# IR_Interface_Board.net
KiCad netlist of a schematic drawn in EAGLE
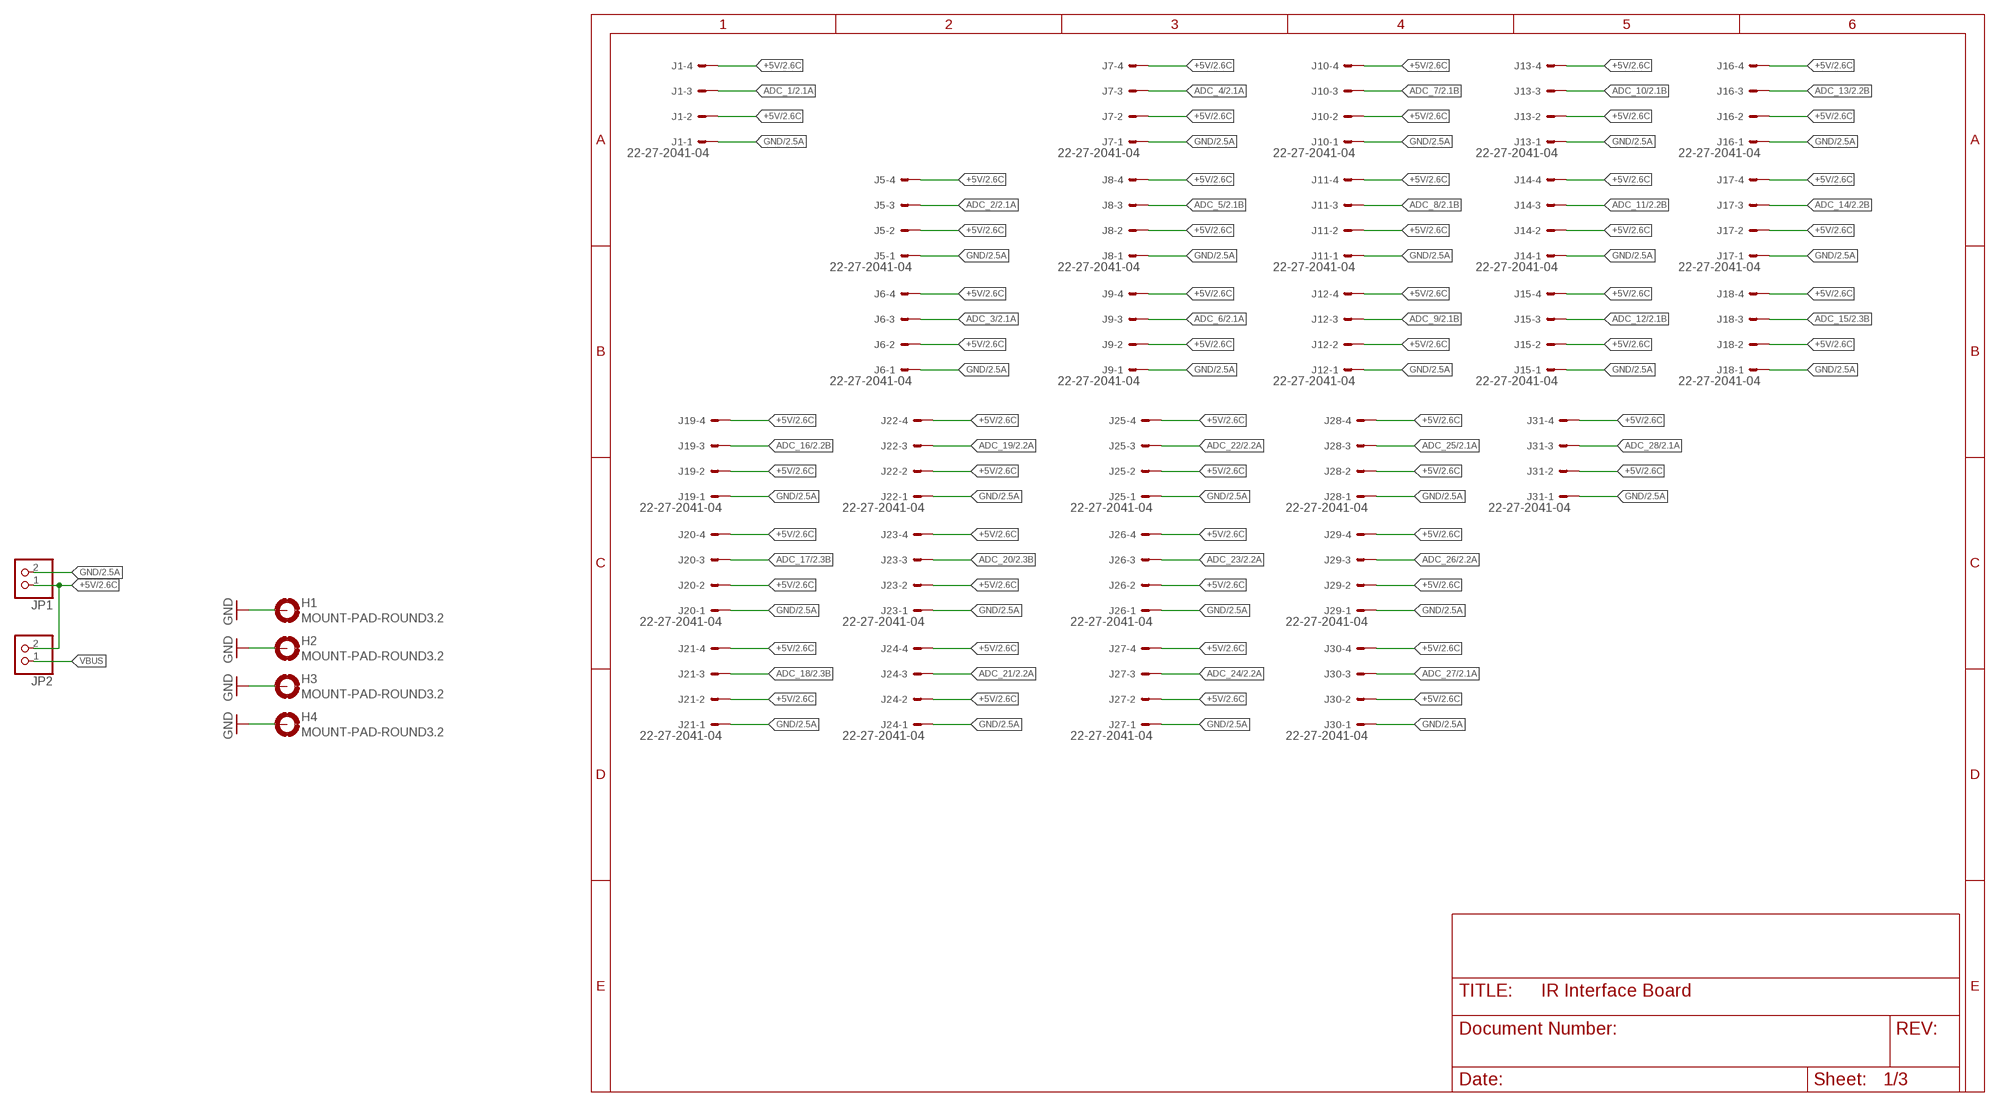
[diagram p0: schematic, sheet 1]
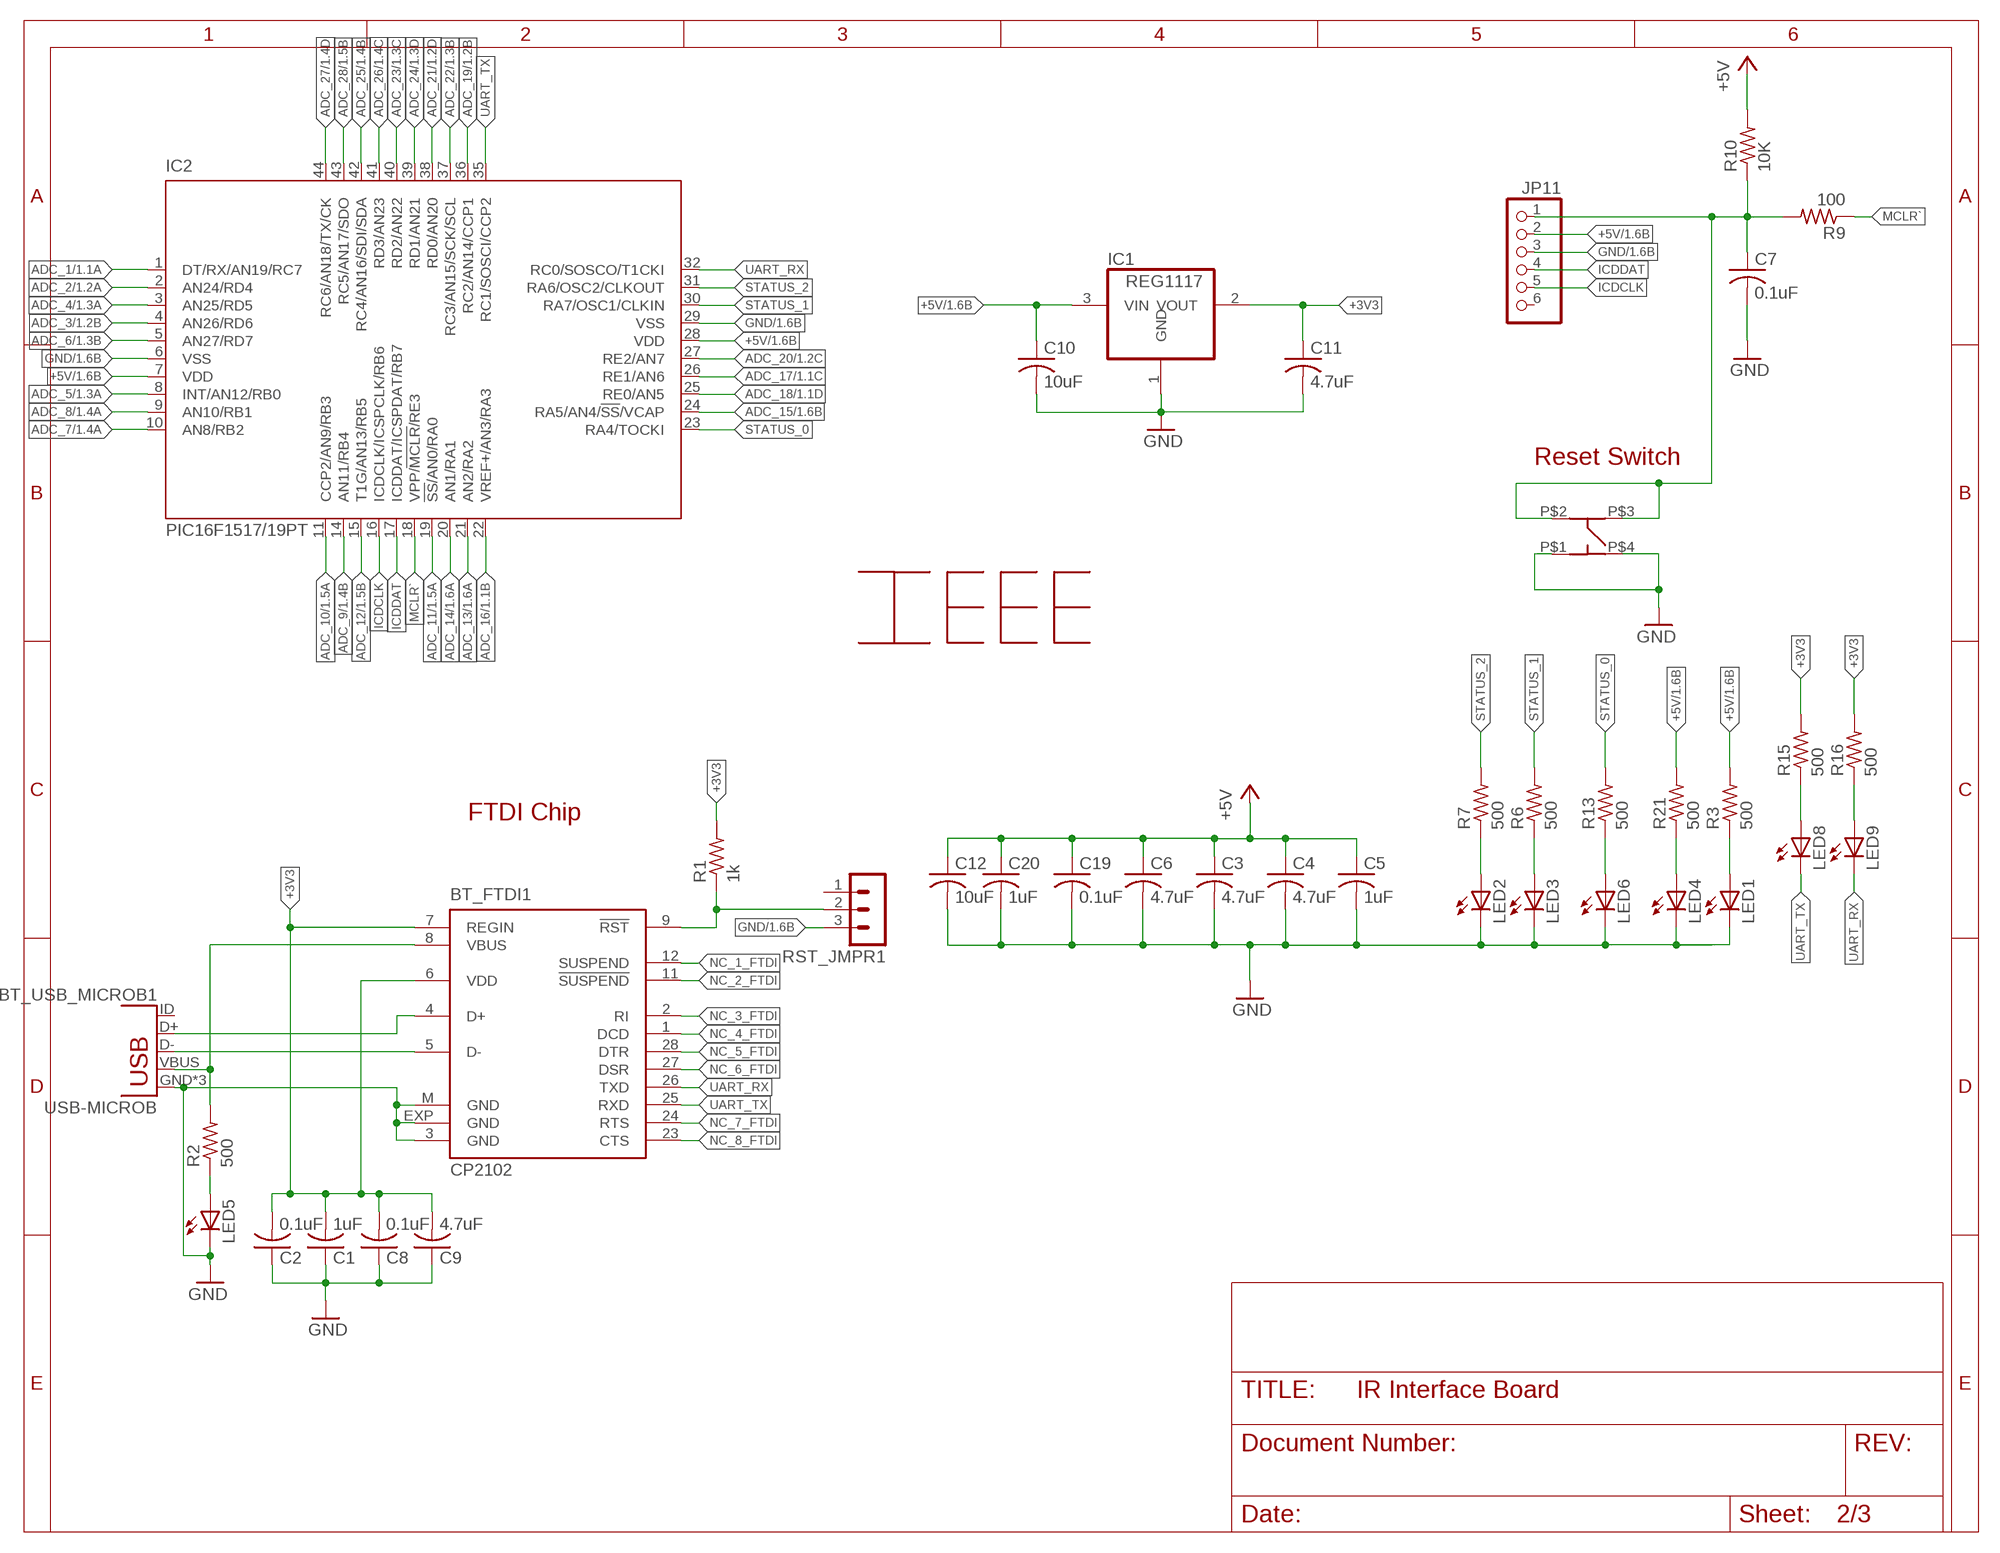
[diagram p1: schematic, sheet 2]
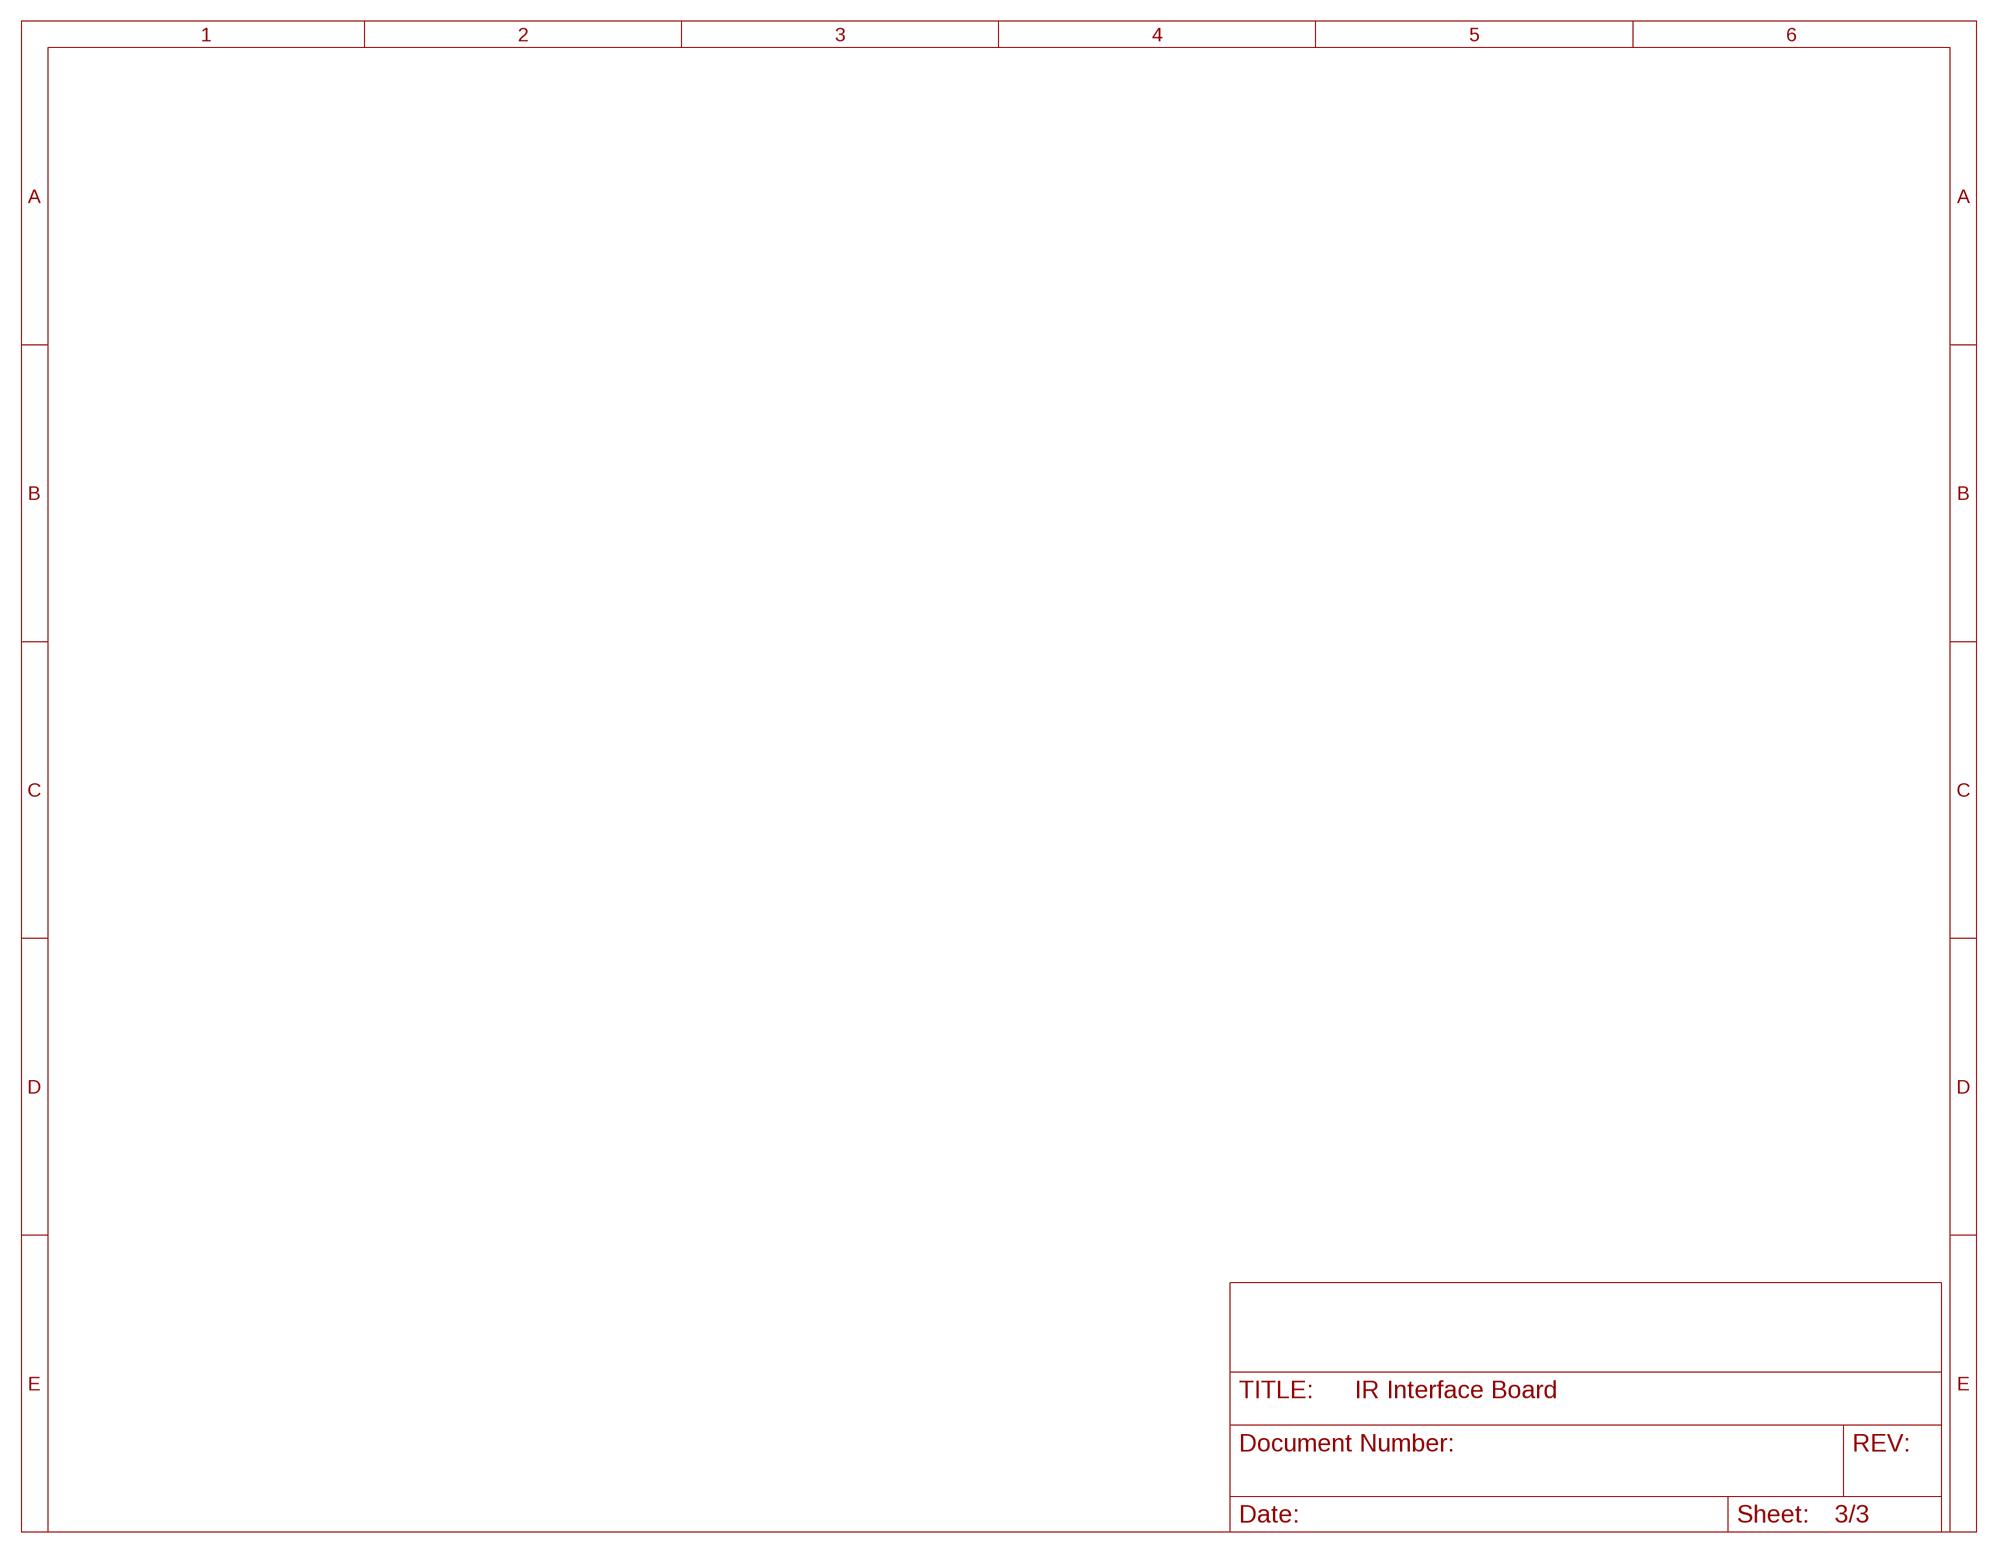
[diagram p2: schematic, sheet 3]

(export (version "E")
  (design (tool "Eeschema 10.0.6"))
  (components
    (comp (ref "H1")
      (value "MOUNT-PAD-ROUND3.2")
      (footprint "eagle-import:3,2-PAD")
      (libsource (lib "eagle-import") (part "MOUNT-PAD-ROUND3.2"))
    )
    (comp (ref "H2")
      (value "MOUNT-PAD-ROUND3.2")
      (footprint "eagle-import:3,2-PAD")
      (libsource (lib "eagle-import") (part "MOUNT-PAD-ROUND3.2"))
    )
    (comp (ref "H3")
      (value "MOUNT-PAD-ROUND3.2")
      (footprint "eagle-import:3,2-PAD")
      (libsource (lib "eagle-import") (part "MOUNT-PAD-ROUND3.2"))
    )
    (comp (ref "H4")
      (value "MOUNT-PAD-ROUND3.2")
      (footprint "eagle-import:3,2-PAD")
      (libsource (lib "eagle-import") (part "MOUNT-PAD-ROUND3.2"))
    )
    (comp (ref "J1")
      (value "22-27-2041-04")
      (footprint "eagle-import:6410-04")
      (libsource (lib "eagle-import") (part "22-?-0427-2041"))
    )
    (comp (ref "J5")
      (value "22-27-2041-04")
      (footprint "eagle-import:6410-04")
      (libsource (lib "eagle-import") (part "22-?-0427-2041"))
    )
    (comp (ref "J6")
      (value "22-27-2041-04")
      (footprint "eagle-import:6410-04")
      (libsource (lib "eagle-import") (part "22-?-0427-2041"))
    )
    (comp (ref "J7")
      (value "22-27-2041-04")
      (footprint "eagle-import:6410-04")
      (libsource (lib "eagle-import") (part "22-?-0427-2041"))
    )
    (comp (ref "J8")
      (value "22-27-2041-04")
      (footprint "eagle-import:6410-04")
      (libsource (lib "eagle-import") (part "22-?-0427-2041"))
    )
    (comp (ref "J9")
      (value "22-27-2041-04")
      (footprint "eagle-import:6410-04")
      (libsource (lib "eagle-import") (part "22-?-0427-2041"))
    )
    (comp (ref "J10")
      (value "22-27-2041-04")
      (footprint "eagle-import:6410-04")
      (libsource (lib "eagle-import") (part "22-?-0427-2041"))
    )
    (comp (ref "J11")
      (value "22-27-2041-04")
      (footprint "eagle-import:6410-04")
      (libsource (lib "eagle-import") (part "22-?-0427-2041"))
    )
    (comp (ref "J12")
      (value "22-27-2041-04")
      (footprint "eagle-import:6410-04")
      (libsource (lib "eagle-import") (part "22-?-0427-2041"))
    )
    (comp (ref "J13")
      (value "22-27-2041-04")
      (footprint "eagle-import:6410-04")
      (libsource (lib "eagle-import") (part "22-?-0427-2041"))
    )
    (comp (ref "J14")
      (value "22-27-2041-04")
      (footprint "eagle-import:6410-04")
      (libsource (lib "eagle-import") (part "22-?-0427-2041"))
    )
    (comp (ref "J15")
      (value "22-27-2041-04")
      (footprint "eagle-import:6410-04")
      (libsource (lib "eagle-import") (part "22-?-0427-2041"))
    )
    (comp (ref "J16")
      (value "22-27-2041-04")
      (footprint "eagle-import:6410-04")
      (libsource (lib "eagle-import") (part "22-?-0427-2041"))
    )
    (comp (ref "J17")
      (value "22-27-2041-04")
      (footprint "eagle-import:6410-04")
      (libsource (lib "eagle-import") (part "22-?-0427-2041"))
    )
    (comp (ref "J18")
      (value "22-27-2041-04")
      (footprint "eagle-import:6410-04")
      (libsource (lib "eagle-import") (part "22-?-0427-2041"))
    )
    (comp (ref "J19")
      (value "22-27-2041-04")
      (footprint "eagle-import:6410-04")
      (libsource (lib "eagle-import") (part "22-?-0427-2041"))
    )
    (comp (ref "J20")
      (value "22-27-2041-04")
      (footprint "eagle-import:6410-04")
      (libsource (lib "eagle-import") (part "22-?-0427-2041"))
    )
    (comp (ref "J21")
      (value "22-27-2041-04")
      (footprint "eagle-import:6410-04")
      (libsource (lib "eagle-import") (part "22-?-0427-2041"))
    )
    (comp (ref "J22")
      (value "22-27-2041-04")
      (footprint "eagle-import:6410-04")
      (libsource (lib "eagle-import") (part "22-?-0427-2041"))
    )
    (comp (ref "J23")
      (value "22-27-2041-04")
      (footprint "eagle-import:6410-04")
      (libsource (lib "eagle-import") (part "22-?-0427-2041"))
    )
    (comp (ref "J24")
      (value "22-27-2041-04")
      (footprint "eagle-import:6410-04")
      (libsource (lib "eagle-import") (part "22-?-0427-2041"))
    )
    (comp (ref "J25")
      (value "22-27-2041-04")
      (footprint "eagle-import:6410-04")
      (libsource (lib "eagle-import") (part "22-?-0427-2041"))
    )
    (comp (ref "J26")
      (value "22-27-2041-04")
      (footprint "eagle-import:6410-04")
      (libsource (lib "eagle-import") (part "22-?-0427-2041"))
    )
    (comp (ref "J27")
      (value "22-27-2041-04")
      (footprint "eagle-import:6410-04")
      (libsource (lib "eagle-import") (part "22-?-0427-2041"))
    )
    (comp (ref "J28")
      (value "22-27-2041-04")
      (footprint "eagle-import:6410-04")
      (libsource (lib "eagle-import") (part "22-?-0427-2041"))
    )
    (comp (ref "J29")
      (value "22-27-2041-04")
      (footprint "eagle-import:6410-04")
      (libsource (lib "eagle-import") (part "22-?-0427-2041"))
    )
    (comp (ref "J30")
      (value "22-27-2041-04")
      (footprint "eagle-import:6410-04")
      (libsource (lib "eagle-import") (part "22-?-0427-2041"))
    )
    (comp (ref "J31")
      (value "22-27-2041-04")
      (footprint "eagle-import:6410-04")
      (libsource (lib "eagle-import") (part "22-?-0427-2041"))
    )
    (comp (ref "JP1")
      (value "PINHD-1X2")
      (footprint "eagle-import:1X02")
      (libsource (lib "eagle-import") (part "PINHD-1X2"))
    )
    (comp (ref "JP2")
      (value "PINHD-1X2")
      (footprint "eagle-import:1X02")
      (libsource (lib "eagle-import") (part "PINHD-1X2"))
    )
    (comp (ref "BT_FTDI1")
      (value "CP2102")
      (footprint "eagle-import:MLP28")
      (fields (field (name "MF") "FARNELL") (field (name "MPN") "CP2102-GM"))
      (libsource (lib "eagle-import") (part "CP2102"))
    )
    (comp (ref "BT_USB_MICROB1")
      (value "USB-MICROB")
      (footprint "eagle-import:USB-MICROB")
      (libsource (lib "eagle-import") (part "USB-MICROB"))
    )
    (comp (ref "C1")
      (value "1uF")
      (footprint "eagle-import:C0805")
      (libsource (lib "eagle-import") (part "C-USC0805"))
    )
    (comp (ref "C2")
      (value "0.1uF")
      (footprint "eagle-import:C0805")
      (libsource (lib "eagle-import") (part "C-USC0805"))
    )
    (comp (ref "C3")
      (value "4.7uF")
      (footprint "eagle-import:C0805")
      (libsource (lib "eagle-import") (part "C-USC0805"))
    )
    (comp (ref "C4")
      (value "4.7uF")
      (footprint "eagle-import:C0805")
      (libsource (lib "eagle-import") (part "C-USC0805"))
    )
    (comp (ref "C5")
      (value "1uF")
      (footprint "eagle-import:C0805")
      (libsource (lib "eagle-import") (part "C-USC0805"))
    )
    (comp (ref "C6")
      (value "4.7uF")
      (footprint "eagle-import:C0805")
      (libsource (lib "eagle-import") (part "C-USC0805"))
    )
    (comp (ref "C7")
      (value "0.1uF")
      (footprint "eagle-import:C0805")
      (libsource (lib "eagle-import") (part "C-USC0805"))
    )
    (comp (ref "C8")
      (value "0.1uF")
      (footprint "eagle-import:C0805")
      (libsource (lib "eagle-import") (part "C-USC0805"))
    )
    (comp (ref "C9")
      (value "4.7uF")
      (footprint "eagle-import:C0805")
      (libsource (lib "eagle-import") (part "C-USC0805"))
    )
    (comp (ref "C10")
      (value "10uF")
      (footprint "eagle-import:C0805")
      (libsource (lib "eagle-import") (part "C-USC0805"))
    )
    (comp (ref "C11")
      (value "4.7uF")
      (footprint "eagle-import:C0805")
      (libsource (lib "eagle-import") (part "C-USC0805"))
    )
    (comp (ref "C12")
      (value "10uF")
      (footprint "eagle-import:C0805")
      (libsource (lib "eagle-import") (part "C-USC0805"))
    )
    (comp (ref "C19")
      (value "0.1uF")
      (footprint "eagle-import:C0805")
      (libsource (lib "eagle-import") (part "C-USC0805"))
    )
    (comp (ref "C20")
      (value "1uF")
      (footprint "eagle-import:C0805")
      (libsource (lib "eagle-import") (part "C-USC0805"))
    )
    (comp (ref "IC1")
      (value "REG1117")
      (footprint "eagle-import:SOT223")
      (libsource (lib "eagle-import") (part "REG1117"))
    )
    (comp (ref "IC2")
      (value "PIC16F1517/19PT")
      (footprint "eagle-import:TQFP44")
      (libsource (lib "eagle-import") (part "PIC16F1517/19PT"))
    )
    (comp (ref "JP11")
      (value "PINHD-1X6/90")
      (footprint "eagle-import:1X06_90")
      (libsource (lib "eagle-import") (part "PINHD-1X6/90"))
    )
    (comp (ref "LED1")
      (value "LEDSML0603")
      (footprint "eagle-import:SML0603")
      (libsource (lib "eagle-import") (part "LEDSML0603"))
    )
    (comp (ref "LED2")
      (value "LEDSML0603")
      (footprint "eagle-import:SML0603")
      (libsource (lib "eagle-import") (part "LEDSML0603"))
    )
    (comp (ref "LED3")
      (value "LEDSML0603")
      (footprint "eagle-import:SML0603")
      (libsource (lib "eagle-import") (part "LEDSML0603"))
    )
    (comp (ref "LED4")
      (value "LEDSML0603")
      (footprint "eagle-import:SML0603")
      (libsource (lib "eagle-import") (part "LEDSML0603"))
    )
    (comp (ref "LED5")
      (value "LEDSML0603")
      (footprint "eagle-import:SML0603")
      (libsource (lib "eagle-import") (part "LEDSML0603"))
    )
    (comp (ref "LED6")
      (value "LEDSML0603")
      (footprint "eagle-import:SML0603")
      (libsource (lib "eagle-import") (part "LEDSML0603"))
    )
    (comp (ref "LED8")
      (value "LEDSML0603")
      (footprint "eagle-import:SML0603")
      (libsource (lib "eagle-import") (part "LEDSML0603"))
    )
    (comp (ref "LED9")
      (value "LEDSML0603")
      (footprint "eagle-import:SML0603")
      (libsource (lib "eagle-import") (part "LEDSML0603"))
    )
    (comp (ref "R1")
      (value "1k")
      (footprint "eagle-import:R0805")
      (libsource (lib "eagle-import") (part "resistor_R-US_R0805"))
    )
    (comp (ref "R2")
      (value "500")
      (footprint "eagle-import:R0805")
      (libsource (lib "eagle-import") (part "R-US_R0805"))
    )
    (comp (ref "R3")
      (value "500")
      (footprint "eagle-import:R0805")
      (libsource (lib "eagle-import") (part "R-US_R0805"))
    )
    (comp (ref "R6")
      (value "500")
      (footprint "eagle-import:R0805")
      (libsource (lib "eagle-import") (part "R-US_R0805"))
    )
    (comp (ref "R7")
      (value "500")
      (footprint "eagle-import:R0805")
      (libsource (lib "eagle-import") (part "R-US_R0805"))
    )
    (comp (ref "R9")
      (value "100")
      (footprint "eagle-import:R0805")
      (libsource (lib "eagle-import") (part "R-US_R0805"))
    )
    (comp (ref "R10")
      (value "10K")
      (footprint "eagle-import:R0805")
      (libsource (lib "eagle-import") (part "R-US_R0805"))
    )
    (comp (ref "R13")
      (value "500")
      (footprint "eagle-import:R0805")
      (libsource (lib "eagle-import") (part "R-US_R0805"))
    )
    (comp (ref "R15")
      (value "500")
      (footprint "eagle-import:R0805")
      (libsource (lib "eagle-import") (part "R-US_R0805"))
    )
    (comp (ref "R16")
      (value "500")
      (footprint "eagle-import:R0805")
      (libsource (lib "eagle-import") (part "R-US_R0805"))
    )
    (comp (ref "R21")
      (value "500")
      (footprint "eagle-import:R0805")
      (libsource (lib "eagle-import") (part "R-US_R0805"))
    )
    (comp (ref "RST_JMPR1")
      (value "MA03-1")
      (footprint "eagle-import:MA03-1")
      (libsource (lib "eagle-import") (part "MA03-1"))
    )
    (comp (ref "TOUCH_RESET")
      (value "RESET")
      (footprint "eagle-import:MC32882_FINAL")
      (libsource (lib "eagle-import") (part "MC32882_SW"))
    )
    (comp (ref "U$1")
      (value "LOGO")
      (footprint "eagle-import:IEEE-LOGO")
      (libsource (lib "eagle-import") (part "LOGO"))
    )
  )
  (nets
    (net (code "1") (name "+3V3") (class "Default")
      (node (ref "BT_FTDI1") (pin "6") (pinfunction "VDD_6") (pintype "power_in"))
      (node (ref "BT_FTDI1") (pin "7") (pinfunction "REGIN_7") (pintype "passive"))
      (node (ref "C1") (pin "2") (pinfunction "2_2") (pintype "passive"))
      (node (ref "C11") (pin "1") (pinfunction "1_1") (pintype "passive"))
      (node (ref "C2") (pin "2") (pinfunction "2_2") (pintype "passive"))
      (node (ref "C8") (pin "2") (pinfunction "2_2") (pintype "passive"))
      (node (ref "C9") (pin "2") (pinfunction "2_2") (pintype "passive"))
      (node (ref "IC1") (pin "2") (pinfunction "VOUT_2") (pintype "output"))
      (node (ref "R1") (pin "2") (pinfunction "2_2") (pintype "passive"))
      (node (ref "R15") (pin "2") (pinfunction "2_2") (pintype "passive"))
      (node (ref "R16") (pin "2") (pinfunction "2_2") (pintype "passive"))
    )
    (net (code "2") (name "+5V") (class "Default")
      (node (ref "C10") (pin "1") (pinfunction "1_1") (pintype "passive"))
      (node (ref "C12") (pin "1") (pinfunction "1_1") (pintype "passive"))
      (node (ref "C19") (pin "1") (pinfunction "1_1") (pintype "passive"))
      (node (ref "C20") (pin "1") (pinfunction "1_1") (pintype "passive"))
      (node (ref "C3") (pin "1") (pinfunction "1_1") (pintype "passive"))
      (node (ref "C4") (pin "1") (pinfunction "1_1") (pintype "passive"))
      (node (ref "C5") (pin "1") (pinfunction "1_1") (pintype "passive"))
      (node (ref "C6") (pin "1") (pinfunction "1_1") (pintype "passive"))
      (node (ref "IC1") (pin "3") (pinfunction "VIN_3") (pintype "input"))
      (node (ref "IC2") (pin "28") (pinfunction "VDD_28") (pintype "power_in"))
      (node (ref "IC2") (pin "7") (pinfunction "VDD_7") (pintype "power_in"))
      (node (ref "J1") (pin "2") (pinfunction "S_2") (pintype "passive"))
      (node (ref "J1") (pin "4") (pinfunction "S_4") (pintype "passive"))
      (node (ref "J10") (pin "2") (pinfunction "S_2") (pintype "passive"))
      (node (ref "J10") (pin "4") (pinfunction "S_4") (pintype "passive"))
      (node (ref "J11") (pin "2") (pinfunction "S_2") (pintype "passive"))
      (node (ref "J11") (pin "4") (pinfunction "S_4") (pintype "passive"))
      (node (ref "J12") (pin "2") (pinfunction "S_2") (pintype "passive"))
      (node (ref "J12") (pin "4") (pinfunction "S_4") (pintype "passive"))
      (node (ref "J13") (pin "2") (pinfunction "S_2") (pintype "passive"))
      (node (ref "J13") (pin "4") (pinfunction "S_4") (pintype "passive"))
      (node (ref "J14") (pin "2") (pinfunction "S_2") (pintype "passive"))
      (node (ref "J14") (pin "4") (pinfunction "S_4") (pintype "passive"))
      (node (ref "J15") (pin "2") (pinfunction "S_2") (pintype "passive"))
      (node (ref "J15") (pin "4") (pinfunction "S_4") (pintype "passive"))
      (node (ref "J16") (pin "2") (pinfunction "S_2") (pintype "passive"))
      (node (ref "J16") (pin "4") (pinfunction "S_4") (pintype "passive"))
      (node (ref "J17") (pin "2") (pinfunction "S_2") (pintype "passive"))
      (node (ref "J17") (pin "4") (pinfunction "S_4") (pintype "passive"))
      (node (ref "J18") (pin "2") (pinfunction "S_2") (pintype "passive"))
      (node (ref "J18") (pin "4") (pinfunction "S_4") (pintype "passive"))
      (node (ref "J19") (pin "2") (pinfunction "S_2") (pintype "passive"))
      (node (ref "J19") (pin "4") (pinfunction "S_4") (pintype "passive"))
      (node (ref "J20") (pin "2") (pinfunction "S_2") (pintype "passive"))
      (node (ref "J20") (pin "4") (pinfunction "S_4") (pintype "passive"))
      (node (ref "J21") (pin "2") (pinfunction "S_2") (pintype "passive"))
      (node (ref "J21") (pin "4") (pinfunction "S_4") (pintype "passive"))
      (node (ref "J22") (pin "2") (pinfunction "S_2") (pintype "passive"))
      (node (ref "J22") (pin "4") (pinfunction "S_4") (pintype "passive"))
      (node (ref "J23") (pin "2") (pinfunction "S_2") (pintype "passive"))
      (node (ref "J23") (pin "4") (pinfunction "S_4") (pintype "passive"))
      (node (ref "J24") (pin "2") (pinfunction "S_2") (pintype "passive"))
      (node (ref "J24") (pin "4") (pinfunction "S_4") (pintype "passive"))
      (node (ref "J25") (pin "2") (pinfunction "S_2") (pintype "passive"))
      (node (ref "J25") (pin "4") (pinfunction "S_4") (pintype "passive"))
      (node (ref "J26") (pin "2") (pinfunction "S_2") (pintype "passive"))
      (node (ref "J26") (pin "4") (pinfunction "S_4") (pintype "passive"))
      (node (ref "J27") (pin "2") (pinfunction "S_2") (pintype "passive"))
      (node (ref "J27") (pin "4") (pinfunction "S_4") (pintype "passive"))
      (node (ref "J28") (pin "2") (pinfunction "S_2") (pintype "passive"))
      (node (ref "J28") (pin "4") (pinfunction "S_4") (pintype "passive"))
      (node (ref "J29") (pin "2") (pinfunction "S_2") (pintype "passive"))
      (node (ref "J29") (pin "4") (pinfunction "S_4") (pintype "passive"))
      (node (ref "J30") (pin "2") (pinfunction "S_2") (pintype "passive"))
      (node (ref "J30") (pin "4") (pinfunction "S_4") (pintype "passive"))
      (node (ref "J31") (pin "2") (pinfunction "S_2") (pintype "passive"))
      (node (ref "J31") (pin "4") (pinfunction "S_4") (pintype "passive"))
      (node (ref "J5") (pin "2") (pinfunction "S_2") (pintype "passive"))
      (node (ref "J5") (pin "4") (pinfunction "S_4") (pintype "passive"))
      (node (ref "J6") (pin "2") (pinfunction "S_2") (pintype "passive"))
      (node (ref "J6") (pin "4") (pinfunction "S_4") (pintype "passive"))
      (node (ref "J7") (pin "2") (pinfunction "S_2") (pintype "passive"))
      (node (ref "J7") (pin "4") (pinfunction "S_4") (pintype "passive"))
      (node (ref "J8") (pin "2") (pinfunction "S_2") (pintype "passive"))
      (node (ref "J8") (pin "4") (pinfunction "S_4") (pintype "passive"))
      (node (ref "J9") (pin "2") (pinfunction "S_2") (pintype "passive"))
      (node (ref "J9") (pin "4") (pinfunction "S_4") (pintype "passive"))
      (node (ref "JP1") (pin "1") (pinfunction "1_1") (pintype "passive"))
      (node (ref "JP11") (pin "2") (pinfunction "2_2") (pintype "passive"))
      (node (ref "JP2") (pin "2") (pinfunction "2_2") (pintype "passive"))
      (node (ref "R10") (pin "2") (pinfunction "2_2") (pintype "passive"))
      (node (ref "R21") (pin "2") (pinfunction "2_2") (pintype "passive"))
      (node (ref "R3") (pin "2") (pinfunction "2_2") (pintype "passive"))
    )
    (net (code "3") (name "ADC_1") (class "Default")
      (node (ref "IC2") (pin "1") (pinfunction "DT/RX/AN19/RC7_1") (pintype "bidirectional"))
      (node (ref "J1") (pin "3") (pinfunction "S_3") (pintype "passive"))
    )
    (net (code "4") (name "ADC_2") (class "Default")
      (node (ref "IC2") (pin "2") (pinfunction "AN24/RD4_2") (pintype "bidirectional"))
      (node (ref "J5") (pin "3") (pinfunction "S_3") (pintype "passive"))
    )
    (net (code "5") (name "ADC_3") (class "Default")
      (node (ref "IC2") (pin "4") (pinfunction "AN26/RD6_4") (pintype "bidirectional"))
      (node (ref "J6") (pin "3") (pinfunction "S_3") (pintype "passive"))
    )
    (net (code "6") (name "ADC_4") (class "Default")
      (node (ref "IC2") (pin "3") (pinfunction "AN25/RD5_3") (pintype "bidirectional"))
      (node (ref "J7") (pin "3") (pinfunction "S_3") (pintype "passive"))
    )
    (net (code "7") (name "ADC_5") (class "Default")
      (node (ref "IC2") (pin "8") (pinfunction "INT/AN12/RB0_8") (pintype "bidirectional"))
      (node (ref "J8") (pin "3") (pinfunction "S_3") (pintype "passive"))
    )
    (net (code "8") (name "ADC_6") (class "Default")
      (node (ref "IC2") (pin "5") (pinfunction "AN27/RD7_5") (pintype "bidirectional"))
      (node (ref "J9") (pin "3") (pinfunction "S_3") (pintype "passive"))
    )
    (net (code "9") (name "ADC_7") (class "Default")
      (node (ref "IC2") (pin "10") (pinfunction "AN8/RB2_10") (pintype "bidirectional"))
      (node (ref "J10") (pin "3") (pinfunction "S_3") (pintype "passive"))
    )
    (net (code "10") (name "ADC_8") (class "Default")
      (node (ref "IC2") (pin "9") (pinfunction "AN10/RB1_9") (pintype "bidirectional"))
      (node (ref "J11") (pin "3") (pinfunction "S_3") (pintype "passive"))
    )
    (net (code "11") (name "ADC_9") (class "Default")
      (node (ref "IC2") (pin "14") (pinfunction "AN11/RB4_14") (pintype "bidirectional"))
      (node (ref "J12") (pin "3") (pinfunction "S_3") (pintype "passive"))
    )
    (net (code "12") (name "ADC_10") (class "Default")
      (node (ref "IC2") (pin "11") (pinfunction "CCP2/AN9/RB3_11") (pintype "bidirectional"))
      (node (ref "J13") (pin "3") (pinfunction "S_3") (pintype "passive"))
    )
    (net (code "13") (name "ADC_11") (class "Default")
      (node (ref "IC2") (pin "19") (pinfunction "~{SS}/AN0/RA0_19") (pintype "bidirectional"))
      (node (ref "J14") (pin "3") (pinfunction "S_3") (pintype "passive"))
    )
    (net (code "14") (name "ADC_12") (class "Default")
      (node (ref "IC2") (pin "15") (pinfunction "T1G/AN13/RB5_15") (pintype "bidirectional"))
      (node (ref "J15") (pin "3") (pinfunction "S_3") (pintype "passive"))
    )
    (net (code "15") (name "ADC_13") (class "Default")
      (node (ref "IC2") (pin "21") (pinfunction "AN2/RA2_21") (pintype "bidirectional"))
      (node (ref "J16") (pin "3") (pinfunction "S_3") (pintype "passive"))
    )
    (net (code "16") (name "ADC_14") (class "Default")
      (node (ref "IC2") (pin "20") (pinfunction "AN1/RA1_20") (pintype "bidirectional"))
      (node (ref "J17") (pin "3") (pinfunction "S_3") (pintype "passive"))
    )
    (net (code "17") (name "ADC_15") (class "Default")
      (node (ref "IC2") (pin "24") (pinfunction "RA5/AN4/~{SS}/VCAP_24") (pintype "bidirectional"))
      (node (ref "J18") (pin "3") (pinfunction "S_3") (pintype "passive"))
    )
    (net (code "18") (name "ADC_16") (class "Default")
      (node (ref "IC2") (pin "22") (pinfunction "VREF+/AN3/RA3_22") (pintype "bidirectional"))
      (node (ref "J19") (pin "3") (pinfunction "S_3") (pintype "passive"))
    )
    (net (code "19") (name "ADC_17") (class "Default")
      (node (ref "IC2") (pin "26") (pinfunction "RE1/AN6_26") (pintype "bidirectional"))
      (node (ref "J20") (pin "3") (pinfunction "S_3") (pintype "passive"))
    )
    (net (code "20") (name "ADC_18") (class "Default")
      (node (ref "IC2") (pin "25") (pinfunction "RE0/AN5_25") (pintype "bidirectional"))
      (node (ref "J21") (pin "3") (pinfunction "S_3") (pintype "passive"))
    )
    (net (code "21") (name "ADC_19") (class "Default")
      (node (ref "IC2") (pin "36") (pinfunction "RC2/AN14/CCP1_36") (pintype "bidirectional"))
      (node (ref "J22") (pin "3") (pinfunction "S_3") (pintype "passive"))
    )
    (net (code "22") (name "ADC_20") (class "Default")
      (node (ref "IC2") (pin "27") (pinfunction "RE2/AN7_27") (pintype "bidirectional"))
      (node (ref "J23") (pin "3") (pinfunction "S_3") (pintype "passive"))
    )
    (net (code "23") (name "ADC_21") (class "Default")
      (node (ref "IC2") (pin "38") (pinfunction "RD0/AN20_38") (pintype "bidirectional"))
      (node (ref "J24") (pin "3") (pinfunction "S_3") (pintype "passive"))
    )
    (net (code "24") (name "ADC_22") (class "Default")
      (node (ref "IC2") (pin "37") (pinfunction "RC3/AN15/SCK/SCL_37") (pintype "bidirectional"))
      (node (ref "J25") (pin "3") (pinfunction "S_3") (pintype "passive"))
    )
    (net (code "25") (name "ADC_23") (class "Default")
      (node (ref "IC2") (pin "40") (pinfunction "RD2/AN22_40") (pintype "bidirectional"))
      (node (ref "J26") (pin "3") (pinfunction "S_3") (pintype "passive"))
    )
    (net (code "26") (name "ADC_24") (class "Default")
      (node (ref "IC2") (pin "39") (pinfunction "RD1/AN21_39") (pintype "bidirectional"))
      (node (ref "J27") (pin "3") (pinfunction "S_3") (pintype "passive"))
    )
    (net (code "27") (name "ADC_25") (class "Default")
      (node (ref "IC2") (pin "42") (pinfunction "RC4/AN16/SDI/SDA_42") (pintype "bidirectional"))
      (node (ref "J28") (pin "3") (pinfunction "S_3") (pintype "passive"))
    )
    (net (code "28") (name "ADC_26") (class "Default")
      (node (ref "IC2") (pin "41") (pinfunction "RD3/AN23_41") (pintype "bidirectional"))
      (node (ref "J29") (pin "3") (pinfunction "S_3") (pintype "passive"))
    )
    (net (code "29") (name "ADC_27") (class "Default")
      (node (ref "IC2") (pin "44") (pinfunction "RC6/AN18/TX/CK_44") (pintype "bidirectional"))
      (node (ref "J30") (pin "3") (pinfunction "S_3") (pintype "passive"))
    )
    (net (code "30") (name "ADC_28") (class "Default")
      (node (ref "IC2") (pin "43") (pinfunction "RC5/AN17/SDO_43") (pintype "bidirectional"))
      (node (ref "J31") (pin "3") (pinfunction "S_3") (pintype "passive"))
    )
    (net (code "31") (name "GND") (class "Default")
      (node (ref "BT_FTDI1") (pin "3") (pinfunction "GND_3") (pintype "power_in"))
      (node (ref "BT_FTDI1") (pin "EXP") (pinfunction "GND_EXP") (pintype "power_in"))
      (node (ref "BT_FTDI1") (pin "M") (pinfunction "GND_M") (pintype "power_in"))
      (node (ref "BT_USB_MICROB1") (pin "GND") (pinfunction "GND_GND") (pintype "bidirectional"))
      (node (ref "BT_USB_MICROB1") (pin "MT1") (pinfunction "GND_MT1") (pintype "bidirectional"))
      (node (ref "BT_USB_MICROB1") (pin "MT2") (pinfunction "GND_MT2") (pintype "bidirectional"))
      (node (ref "C1") (pin "1") (pinfunction "1_1") (pintype "passive"))
      (node (ref "C10") (pin "2") (pinfunction "2_2") (pintype "passive"))
      (node (ref "C11") (pin "2") (pinfunction "2_2") (pintype "passive"))
      (node (ref "C12") (pin "2") (pinfunction "2_2") (pintype "passive"))
      (node (ref "C19") (pin "2") (pinfunction "2_2") (pintype "passive"))
      (node (ref "C2") (pin "1") (pinfunction "1_1") (pintype "passive"))
      (node (ref "C20") (pin "2") (pinfunction "2_2") (pintype "passive"))
      (node (ref "C3") (pin "2") (pinfunction "2_2") (pintype "passive"))
      (node (ref "C4") (pin "2") (pinfunction "2_2") (pintype "passive"))
      (node (ref "C5") (pin "2") (pinfunction "2_2") (pintype "passive"))
      (node (ref "C6") (pin "2") (pinfunction "2_2") (pintype "passive"))
      (node (ref "C7") (pin "2") (pinfunction "2_2") (pintype "passive"))
      (node (ref "C8") (pin "1") (pinfunction "1_1") (pintype "passive"))
      (node (ref "C9") (pin "1") (pinfunction "1_1") (pintype "passive"))
      (node (ref "H1") (pin "B3,2") (pinfunction "MOUNT_B3,2") (pintype "passive"))
      (node (ref "H2") (pin "B3,2") (pinfunction "MOUNT_B3,2") (pintype "passive"))
      (node (ref "H3") (pin "B3,2") (pinfunction "MOUNT_B3,2") (pintype "passive"))
      (node (ref "H4") (pin "B3,2") (pinfunction "MOUNT_B3,2") (pintype "passive"))
      (node (ref "IC1") (pin "1") (pinfunction "GND_1") (pintype "power_in"))
      (node (ref "IC2") (pin "29") (pinfunction "VSS_29") (pintype "power_in"))
      (node (ref "IC2") (pin "6") (pinfunction "VSS_6") (pintype "power_in"))
      (node (ref "J1") (pin "1") (pinfunction "S_1") (pintype "passive"))
      (node (ref "J10") (pin "1") (pinfunction "S_1") (pintype "passive"))
      (node (ref "J11") (pin "1") (pinfunction "S_1") (pintype "passive"))
      (node (ref "J12") (pin "1") (pinfunction "S_1") (pintype "passive"))
      (node (ref "J13") (pin "1") (pinfunction "S_1") (pintype "passive"))
      (node (ref "J14") (pin "1") (pinfunction "S_1") (pintype "passive"))
      (node (ref "J15") (pin "1") (pinfunction "S_1") (pintype "passive"))
      (node (ref "J16") (pin "1") (pinfunction "S_1") (pintype "passive"))
      (node (ref "J17") (pin "1") (pinfunction "S_1") (pintype "passive"))
      (node (ref "J18") (pin "1") (pinfunction "S_1") (pintype "passive"))
      (node (ref "J19") (pin "1") (pinfunction "S_1") (pintype "passive"))
      (node (ref "J20") (pin "1") (pinfunction "S_1") (pintype "passive"))
      (node (ref "J21") (pin "1") (pinfunction "S_1") (pintype "passive"))
      (node (ref "J22") (pin "1") (pinfunction "S_1") (pintype "passive"))
      (node (ref "J23") (pin "1") (pinfunction "S_1") (pintype "passive"))
      (node (ref "J24") (pin "1") (pinfunction "S_1") (pintype "passive"))
      (node (ref "J25") (pin "1") (pinfunction "S_1") (pintype "passive"))
      (node (ref "J26") (pin "1") (pinfunction "S_1") (pintype "passive"))
      (node (ref "J27") (pin "1") (pinfunction "S_1") (pintype "passive"))
      (node (ref "J28") (pin "1") (pinfunction "S_1") (pintype "passive"))
      (node (ref "J29") (pin "1") (pinfunction "S_1") (pintype "passive"))
      (node (ref "J30") (pin "1") (pinfunction "S_1") (pintype "passive"))
      (node (ref "J31") (pin "1") (pinfunction "S_1") (pintype "passive"))
      (node (ref "J5") (pin "1") (pinfunction "S_1") (pintype "passive"))
      (node (ref "J6") (pin "1") (pinfunction "S_1") (pintype "passive"))
      (node (ref "J7") (pin "1") (pinfunction "S_1") (pintype "passive"))
      (node (ref "J8") (pin "1") (pinfunction "S_1") (pintype "passive"))
      (node (ref "J9") (pin "1") (pinfunction "S_1") (pintype "passive"))
      (node (ref "JP1") (pin "2") (pinfunction "2_2") (pintype "passive"))
      (node (ref "JP11") (pin "3") (pinfunction "3_3") (pintype "passive"))
      (node (ref "LED1") (pin "C") (pinfunction "C_C") (pintype "passive"))
      (node (ref "LED2") (pin "C") (pinfunction "C_C") (pintype "passive"))
      (node (ref "LED3") (pin "C") (pinfunction "C_C") (pintype "passive"))
      (node (ref "LED4") (pin "C") (pinfunction "C_C") (pintype "passive"))
      (node (ref "LED5") (pin "C") (pinfunction "C_C") (pintype "passive"))
      (node (ref "LED6") (pin "C") (pinfunction "C_C") (pintype "passive"))
      (node (ref "RST_JMPR1") (pin "3") (pinfunction "3_3") (pintype "passive"))
      (node (ref "TOUCH_RESET") (pin "P$1") (pinfunction "P1_P$1") (pintype "bidirectional"))
      (node (ref "TOUCH_RESET") (pin "P$4") (pinfunction "P4_P$4") (pintype "bidirectional"))
    )
    (net (code "32") (name "ICDCLK") (class "Default")
      (node (ref "IC2") (pin "16") (pinfunction "ICDCLK/ICSPCLK/RB6_16") (pintype "bidirectional"))
      (node (ref "JP11") (pin "5") (pinfunction "5_5") (pintype "passive"))
    )
    (net (code "33") (name "ICDDAT") (class "Default")
      (node (ref "IC2") (pin "17") (pinfunction "ICDDAT/ICSPDAT/RB7_17") (pintype "bidirectional"))
      (node (ref "JP11") (pin "4") (pinfunction "4_4") (pintype "passive"))
    )
    (net (code "34") (name "MCLR`") (class "Default")
      (node (ref "IC2") (pin "18") (pinfunction "VPP/~{MCLR}/RE3_18") (pintype "input"))
      (node (ref "R9") (pin "1") (pinfunction "1_1") (pintype "passive"))
    )
    (net (code "35") (name "NC_1_FTDI") (class "Default")
      (node (ref "BT_FTDI1") (pin "12") (pinfunction "SUSPEND_12") (pintype "output"))
    )
    (net (code "36") (name "NC_2_FTDI") (class "Default")
      (node (ref "BT_FTDI1") (pin "11") (pinfunction "~{SUSPEND}_11") (pintype "output"))
    )
    (net (code "37") (name "NC_3_FTDI") (class "Default")
      (node (ref "BT_FTDI1") (pin "2") (pinfunction "RI_2") (pintype "input"))
    )
    (net (code "38") (name "NC_4_FTDI") (class "Default")
      (node (ref "BT_FTDI1") (pin "1") (pinfunction "DCD_1") (pintype "input"))
    )
    (net (code "39") (name "NC_5_FTDI") (class "Default")
      (node (ref "BT_FTDI1") (pin "28") (pinfunction "DTR_28") (pintype "output"))
    )
    (net (code "40") (name "NC_6_FTDI") (class "Default")
      (node (ref "BT_FTDI1") (pin "27") (pinfunction "DSR_27") (pintype "input"))
    )
    (net (code "41") (name "NC_7_FTDI") (class "Default")
      (node (ref "BT_FTDI1") (pin "24") (pinfunction "RTS_24") (pintype "output"))
    )
    (net (code "42") (name "NC_8_FTDI") (class "Default")
      (node (ref "BT_FTDI1") (pin "23") (pinfunction "CTS_23") (pintype "input"))
    )
    (net (code "43") (name "Net-(BT_FTDI1-D+)") (class "Default")
      (node (ref "BT_FTDI1") (pin "4") (pinfunction "D+_4") (pintype "bidirectional"))
      (node (ref "BT_USB_MICROB1") (pin "D+") (pinfunction "D+_D+") (pintype "bidirectional"))
    )
    (net (code "44") (name "Net-(BT_FTDI1-D-)") (class "Default")
      (node (ref "BT_FTDI1") (pin "5") (pinfunction "D-_5") (pintype "bidirectional"))
      (node (ref "BT_USB_MICROB1") (pin "D-") (pinfunction "D-_D-") (pintype "bidirectional"))
    )
    (net (code "45") (name "Net-(BT_FTDI1-~{RST})") (class "Default")
      (node (ref "BT_FTDI1") (pin "9") (pinfunction "~{RST}_9") (pintype "bidirectional"))
      (node (ref "R1") (pin "1") (pinfunction "1_1") (pintype "passive"))
      (node (ref "RST_JMPR1") (pin "2") (pinfunction "2_2") (pintype "passive"))
    )
    (net (code "46") (name "Net-(LED1-PadA)") (class "Default")
      (node (ref "LED1") (pin "A") (pinfunction "A_A") (pintype "passive"))
      (node (ref "R3") (pin "1") (pinfunction "1_1") (pintype "passive"))
    )
    (net (code "47") (name "Net-(LED2-PadA)") (class "Default")
      (node (ref "LED2") (pin "A") (pinfunction "A_A") (pintype "passive"))
      (node (ref "R7") (pin "1") (pinfunction "1_1") (pintype "passive"))
    )
    (net (code "48") (name "Net-(LED3-PadA)") (class "Default")
      (node (ref "LED3") (pin "A") (pinfunction "A_A") (pintype "passive"))
      (node (ref "R6") (pin "1") (pinfunction "1_1") (pintype "passive"))
    )
    (net (code "49") (name "Net-(LED4-PadA)") (class "Default")
      (node (ref "LED4") (pin "A") (pinfunction "A_A") (pintype "passive"))
      (node (ref "R21") (pin "1") (pinfunction "1_1") (pintype "passive"))
    )
    (net (code "50") (name "Net-(LED5-PadA)") (class "Default")
      (node (ref "LED5") (pin "A") (pinfunction "A_A") (pintype "passive"))
      (node (ref "R2") (pin "1") (pinfunction "1_1") (pintype "passive"))
    )
    (net (code "51") (name "Net-(LED6-PadA)") (class "Default")
      (node (ref "LED6") (pin "A") (pinfunction "A_A") (pintype "passive"))
      (node (ref "R13") (pin "1") (pinfunction "1_1") (pintype "passive"))
    )
    (net (code "52") (name "Net-(LED8-PadA)") (class "Default")
      (node (ref "LED8") (pin "A") (pinfunction "A_A") (pintype "passive"))
      (node (ref "R15") (pin "1") (pinfunction "1_1") (pintype "passive"))
    )
    (net (code "53") (name "Net-(LED9-PadA)") (class "Default")
      (node (ref "LED9") (pin "A") (pinfunction "A_A") (pintype "passive"))
      (node (ref "R16") (pin "1") (pinfunction "1_1") (pintype "passive"))
    )
    (net (code "54") (name "Net-(TOUCH_RESET-P2)") (class "Default")
      (node (ref "C7") (pin "1") (pinfunction "1_1") (pintype "passive"))
      (node (ref "JP11") (pin "1") (pinfunction "1_1") (pintype "passive"))
      (node (ref "R10") (pin "1") (pinfunction "1_1") (pintype "passive"))
      (node (ref "R9") (pin "2") (pinfunction "2_2") (pintype "passive"))
      (node (ref "TOUCH_RESET") (pin "P$2") (pinfunction "P2_P$2") (pintype "bidirectional"))
      (node (ref "TOUCH_RESET") (pin "P$3") (pinfunction "P3_P$3") (pintype "bidirectional"))
    )
    (net (code "55") (name "STATUS_0") (class "Default")
      (node (ref "IC2") (pin "23") (pinfunction "RA4/TOCKI_23") (pintype "bidirectional"))
      (node (ref "R13") (pin "2") (pinfunction "2_2") (pintype "passive"))
    )
    (net (code "56") (name "STATUS_1") (class "Default")
      (node (ref "IC2") (pin "30") (pinfunction "RA7/OSC1/CLKIN_30") (pintype "bidirectional"))
      (node (ref "R6") (pin "2") (pinfunction "2_2") (pintype "passive"))
    )
    (net (code "57") (name "STATUS_2") (class "Default")
      (node (ref "IC2") (pin "31") (pinfunction "RA6/OSC2/CLKOUT_31") (pintype "bidirectional"))
      (node (ref "R7") (pin "2") (pinfunction "2_2") (pintype "passive"))
    )
    (net (code "58") (name "UART_RX") (class "Default")
      (node (ref "BT_FTDI1") (pin "26") (pinfunction "TXD_26") (pintype "output"))
      (node (ref "IC2") (pin "32") (pinfunction "RC0/SOSCO/T1CKI_32") (pintype "bidirectional"))
      (node (ref "LED9") (pin "C") (pinfunction "C_C") (pintype "passive"))
    )
    (net (code "59") (name "UART_TX") (class "Default")
      (node (ref "BT_FTDI1") (pin "25") (pinfunction "RXD_25") (pintype "input"))
      (node (ref "IC2") (pin "35") (pinfunction "RC1/SOSCI/CCP2_35") (pintype "bidirectional"))
      (node (ref "LED8") (pin "C") (pinfunction "C_C") (pintype "passive"))
    )
    (net (code "60") (name "VBUS") (class "Default")
      (node (ref "BT_FTDI1") (pin "8") (pinfunction "VBUS_8") (pintype "input"))
      (node (ref "BT_USB_MICROB1") (pin "VBUS") (pinfunction "VBUS_VBUS") (pintype "bidirectional"))
      (node (ref "JP2") (pin "1") (pinfunction "1_1") (pintype "passive"))
      (node (ref "R2") (pin "2") (pinfunction "2_2") (pintype "passive"))
    )
    (net (code "61") (name "unconnected-(BT_USB_MICROB1-PadID)") (class "Default")
      (node (ref "BT_USB_MICROB1") (pin "ID") (pinfunction "ID_ID") (pintype "bidirectional"))
    )
    (net (code "62") (name "unconnected-(JP11-Pad6)") (class "Default")
      (node (ref "JP11") (pin "6") (pinfunction "6_6") (pintype "passive"))
    )
    (net (code "63") (name "unconnected-(RST_JMPR1-Pad1)") (class "Default")
      (node (ref "RST_JMPR1") (pin "1") (pinfunction "1_1") (pintype "passive"))
    )
  )
)
